# Ethernet.net
KiCad netlist of a schematic drawn in Altium Designer
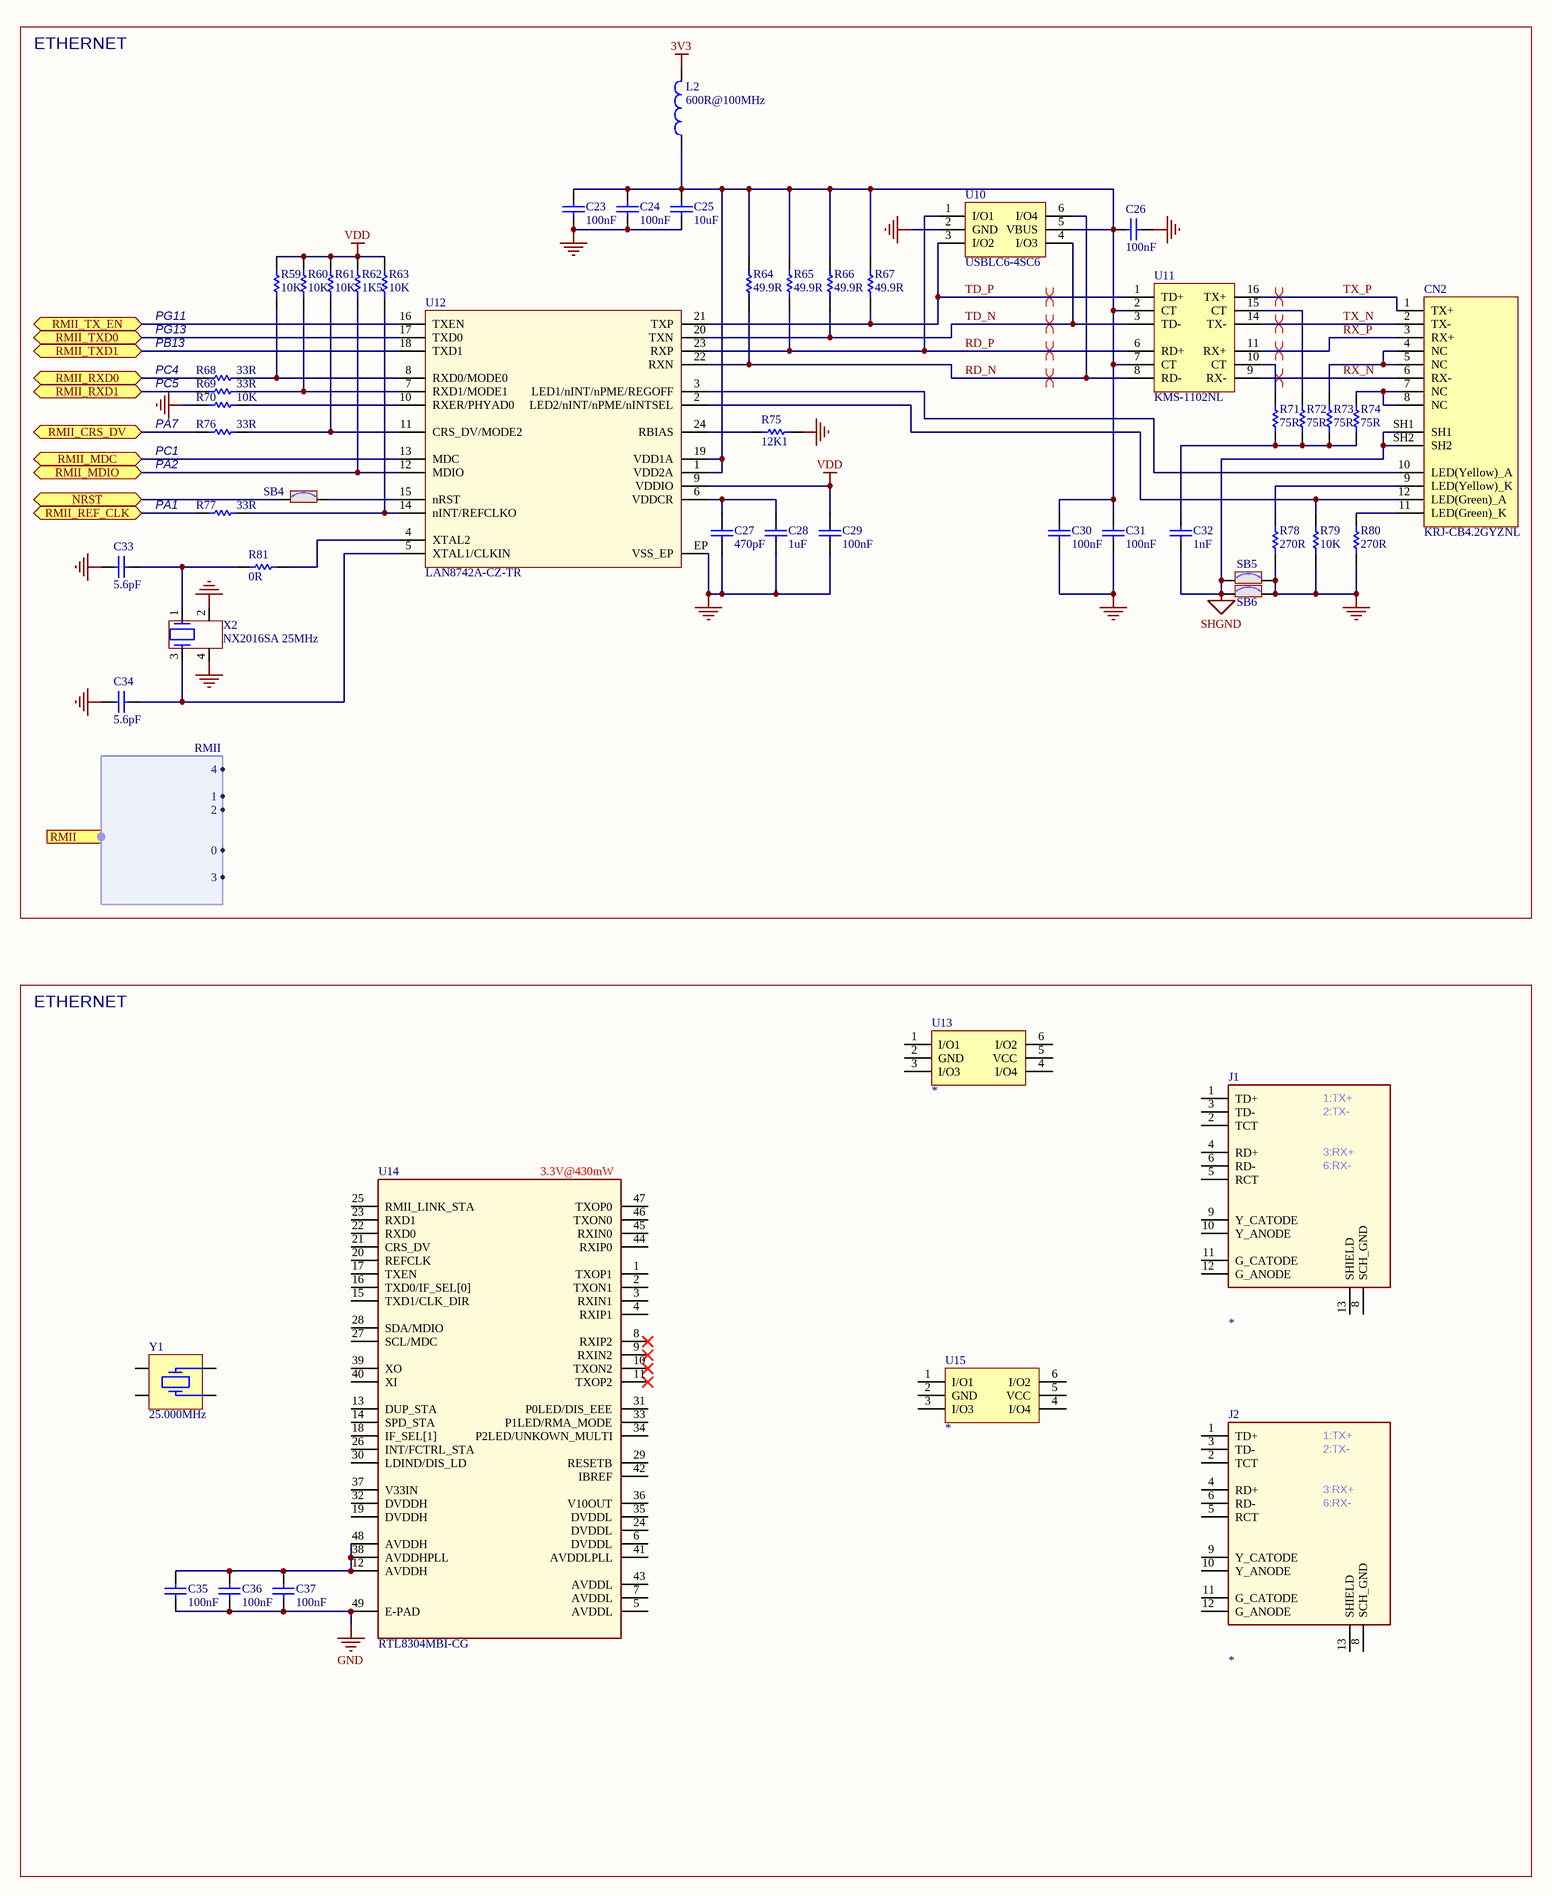
[diagram p0: Ethernet.SchDoc]

(export (version "E")
  (design (tool "Eeschema 10.0.6"))
  (components
    (comp (ref "C23")
      (value "100nF")
      (footprint "C0603")
      (description "Capacitor, MLCC, 100nF, 6V3, X5R, 10%, 0603, T=0,8mm")
      (fields
        (field (name "INTERNAL_PART_NUMBER") "MCD-00237")
        (field (name "MANUFACTURER_PART_NUMBER") "CC0603KRX5R5BB104")
        (field (name "PROVIDED_BY") "SUBCO")
      )
      (libsource (lib "MCD_PARTS_database") (part "Capacitor"))
    )
    (comp (ref "C24")
      (value "100nF")
      (footprint "C0603")
      (description "Capacitor, MLCC, 100nF, 6V3, X5R, 10%, 0603, T=0,8mm")
      (fields
        (field (name "INTERNAL_PART_NUMBER") "MCD-00237")
        (field (name "MANUFACTURER_PART_NUMBER") "CC0603KRX5R5BB104")
        (field (name "PROVIDED_BY") "SUBCO")
      )
      (libsource (lib "MCD_PARTS_database") (part "Capacitor"))
    )
    (comp (ref "C25")
      (value "10uF")
      (footprint "C0603")
      (description "Capacitor, MLCC, 10µF, 10V, X5R, 10%, 0603, T=0.8mm")
      (fields
        (field (name "INTERNAL_PART_NUMBER") "MCD-01124")
        (field (name "MANUFACTURER_PART_NUMBER") "GRM188R61A106KAAL")
        (field (name "PROVIDED_BY") "SUBCO")
      )
      (libsource (lib "MCD_PARTS_database") (part "Capacitor"))
    )
    (comp (ref "C26")
      (value "100nF")
      (footprint "C0603")
      (description "Capacitor, MLCC, 100nF, 6V3, X5R, 10%, 0603, T=0,8mm")
      (fields
        (field (name "INTERNAL_PART_NUMBER") "MCD-00237")
        (field (name "MANUFACTURER_PART_NUMBER") "CC0603KRX5R5BB104")
        (field (name "PROVIDED_BY") "SUBCO")
      )
      (libsource (lib "MCD_PARTS_database") (part "Capacitor"))
    )
    (comp (ref "C27")
      (value "470pF")
      (footprint "C0402")
      (description "Capacitor, MLCC, 470pF, 50V, NPO, 5%, 0402, T=0,5mm")
      (fields
        (field (name "INTERNAL_PART_NUMBER") "MCD-00724")
        (field (name "MANUFACTURER_PART_NUMBER") "CC0402JRNPO9BN471")
        (field (name "PROVIDED_BY") "SUBCO")
      )
      (libsource (lib "MCD_PARTS_database") (part "Capacitor"))
    )
    (comp (ref "C28")
      (value "1uF")
      (footprint "C0402")
      (description "Capacitor, MLCC, 1uF, 6V3, X5R, 10%, 0402, T=0,5mm")
      (fields
        (field (name "INTERNAL_PART_NUMBER") "MCD-00095")
        (field (name "MANUFACTURER_PART_NUMBER") "GRM155R61E105KA12")
        (field (name "PROVIDED_BY") "SUBCO")
      )
      (libsource (lib "MCD_PARTS_database") (part "Capacitor"))
    )
    (comp (ref "C29")
      (value "100nF")
      (footprint "C0603")
      (description "Capacitor, MLCC, 100nF, 6V3, X5R, 10%, 0603, T=0,8mm")
      (fields
        (field (name "INTERNAL_PART_NUMBER") "MCD-00237")
        (field (name "MANUFACTURER_PART_NUMBER") "CC0603KRX5R5BB104")
        (field (name "PROVIDED_BY") "SUBCO")
      )
      (libsource (lib "MCD_PARTS_database") (part "Capacitor"))
    )
    (comp (ref "C30")
      (value "100nF")
      (footprint "C0603")
      (description "Capacitor, MLCC, 100nF, 6V3, X5R, 10%, 0603, T=0,8mm")
      (fields
        (field (name "INTERNAL_PART_NUMBER") "MCD-00237")
        (field (name "MANUFACTURER_PART_NUMBER") "CC0603KRX5R5BB104")
        (field (name "PROVIDED_BY") "SUBCO")
      )
      (libsource (lib "MCD_PARTS_database") (part "Capacitor"))
    )
    (comp (ref "C31")
      (value "100nF")
      (footprint "C0603")
      (description "Capacitor, MLCC, 100nF, 6V3, X5R, 10%, 0603, T=0,8mm")
      (fields
        (field (name "INTERNAL_PART_NUMBER") "MCD-00237")
        (field (name "MANUFACTURER_PART_NUMBER") "CC0603KRX5R5BB104")
        (field (name "PROVIDED_BY") "SUBCO")
      )
      (libsource (lib "MCD_PARTS_database") (part "Capacitor"))
    )
    (comp (ref "C32")
      (value "1nF")
      (footprint "C1206_H1P6")
      (description "Capacitor, MLCC, 1nF, 2KV, X7R, 10%, 1206, T=1,25mm")
      (fields
        (field (name "INTERNAL_PART_NUMBER") "MCD-00722")
        (field (name "MANUFACTURER_PART_NUMBER") "CC1206KKX7RDBB102")
        (field (name "PROVIDED_BY") "SUBCO")
      )
      (libsource (lib "MCD_PARTS_database") (part "Capacitor"))
    )
    (comp (ref "C33")
      (value "5.6pF")
      (footprint "C0402")
      (description "Capacitor, MLCC, 5.6pF, 50V, NPO, 5%, 0402, T=0,5mm")
      (fields
        (field (name "INTERNAL_PART_NUMBER") "MCD-01374")
        (field (name "MANUFACTURER_PART_NUMBER") "CC0402BRNPO9BN5R6")
        (field (name "PROVIDED_BY") "SUBCO")
      )
      (libsource (lib "MCD_PARTS_database") (part "Capacitor"))
    )
    (comp (ref "C34")
      (value "5.6pF")
      (footprint "C0402")
      (description "Capacitor, MLCC, 5.6pF, 50V, NPO, 5%, 0402, T=0,5mm")
      (fields
        (field (name "INTERNAL_PART_NUMBER") "MCD-01374")
        (field (name "MANUFACTURER_PART_NUMBER") "CC0402BRNPO9BN5R6")
        (field (name "PROVIDED_BY") "SUBCO")
      )
      (libsource (lib "MCD_PARTS_database") (part "Capacitor"))
    )
    (comp (ref "C35")
      (value "100nF")
      (footprint "C0603")
      (description "Capacitor, MLCC, 100nF, 6V3, X5R, 10%, 0603, T=0,8mm")
      (fields
        (field (name "INTERNAL_PART_NUMBER") "MCD-00237")
        (field (name "MANUFACTURER_PART_NUMBER") "CC0603KRX5R5BB104")
        (field (name "PROVIDED_BY") "SUBCO")
      )
      (libsource (lib "Motherboard") (part "Capacitor_1"))
    )
    (comp (ref "C36")
      (value "100nF")
      (footprint "C0603")
      (description "Capacitor, MLCC, 100nF, 6V3, X5R, 10%, 0603, T=0,8mm")
      (fields
        (field (name "INTERNAL_PART_NUMBER") "MCD-00237")
        (field (name "MANUFACTURER_PART_NUMBER") "CC0603KRX5R5BB104")
        (field (name "PROVIDED_BY") "SUBCO")
      )
      (libsource (lib "Motherboard") (part "Capacitor_1"))
    )
    (comp (ref "C37")
      (value "100nF")
      (footprint "C0603")
      (description "Capacitor, MLCC, 100nF, 6V3, X5R, 10%, 0603, T=0,8mm")
      (fields
        (field (name "INTERNAL_PART_NUMBER") "MCD-00237")
        (field (name "MANUFACTURER_PART_NUMBER") "CC0603KRX5R5BB104")
        (field (name "PROVIDED_BY") "SUBCO")
      )
      (libsource (lib "Motherboard") (part "Capacitor_1"))
    )
    (comp (ref "CN2")
      (value "KRJ-CB4.2GYZNL")
      (footprint "CON_RJ45_DGKYD_KRJ-CB4.2GYZNL")
      (description "RJ45 jack, single port, with LEDS, Metal shielded dip low profile")
      (fields
        (field (name "INTERNAL_PART_NUMBER") "MCD-00717")
        (field (name "MANUFACTURER") "DONGGUAN KEYOUDA ELECTRONIC TECHNOLOGY")
        (field (name "PROVIDED_BY") "SUBCO")
      )
      (libsource (lib "MCD_PARTS_database") (part "RJ45_KRJ-CB4.2GYZNL"))
    )
    (comp (ref "J1")
      (value "*")
      (footprint "L829-1J1T-43")
      (description "CONN MAGJACK 1PORT SHLD 1000BT")
      (fields
        (field (name "MANUFACTURER") "Bel Fuse Inc")
        (field (name "MANUFACTURER PART NUMBER") "L829-1J1T-43")
        (field (name ".CHECKED PCB") "RF")
        (field (name ".CHECKED SCH") "RF")
      )
      (libsource (lib "Motherboard") (part "51F-1203GYDZ2NL"))
    )
    (comp (ref "J2")
      (value "*")
      (footprint "L829-1J1T-43")
      (description "CONN MAGJACK 1PORT SHLD 1000BT")
      (fields
        (field (name "MANUFACTURER") "Bel Fuse Inc")
        (field (name "MANUFACTURER PART NUMBER") "L829-1J1T-43")
        (field (name ".CHECKED PCB") "RF")
        (field (name ".CHECKED SCH") "RF")
      )
      (libsource (lib "Motherboard") (part "51F-1203GYDZ2NL"))
    )
    (comp (ref "L2")
      (value "600R@100MHz")
      (footprint "L0603")
      (description "SMD Chip ferrite bead, 600R@100MHz +/-25%, 350mA, 500mohm DC, 0603, T=0.8mm")
      (fields
        (field (name "INTERNAL_PART_NUMBER") "MCD-00047")
        (field (name "MANUFACTURER_PART_NUMBER") "FCM1608KF-601T03")
        (field (name "PROVIDED_BY") "SUBCO")
      )
      (libsource (lib "MCD_PARTS_database") (part "BEAD"))
    )
    (comp (ref "R59")
      (value "10K")
      (footprint "R0402")
      (description "Resistor,10K,0402,1%,1/16W")
      (fields
        (field (name "INTERNAL_PART_NUMBER") "MCD-00053")
        (field (name "MANUFACTURER_PART_NUMBER") "RC0402FR-0710KL")
        (field (name "PROVIDED_BY") "SUBCO")
      )
      (libsource (lib "MCD_PARTS_database") (part "Resistor"))
    )
    (comp (ref "R60")
      (value "10K")
      (footprint "R0402")
      (description "Resistor,10K,0402,1%,1/16W")
      (fields
        (field (name "INTERNAL_PART_NUMBER") "MCD-00053")
        (field (name "MANUFACTURER_PART_NUMBER") "RC0402FR-0710KL")
        (field (name "PROVIDED_BY") "SUBCO")
      )
      (libsource (lib "MCD_PARTS_database") (part "Resistor"))
    )
    (comp (ref "R61")
      (value "10K")
      (footprint "R0402")
      (description "Resistor,10K,0402,1%,1/16W")
      (fields
        (field (name "INTERNAL_PART_NUMBER") "MCD-00053")
        (field (name "MANUFACTURER_PART_NUMBER") "RC0402FR-0710KL")
        (field (name "PROVIDED_BY") "SUBCO")
      )
      (libsource (lib "MCD_PARTS_database") (part "Resistor"))
    )
    (comp (ref "R62")
      (value "1K5")
      (footprint "R0402")
      (description "Resistor,1K5,0402,1%,1/16W")
      (fields
        (field (name "INTERNAL_PART_NUMBER") "MCD-00068")
        (field (name "MANUFACTURER_PART_NUMBER") "RC0402FR-071K5L")
        (field (name "PROVIDED_BY") "SUBCO")
      )
      (libsource (lib "MCD_PARTS_database") (part "Resistor"))
    )
    (comp (ref "R63")
      (value "10K")
      (footprint "R0402")
      (description "Resistor,10K,0402,1%,1/16W")
      (fields
        (field (name "INTERNAL_PART_NUMBER") "MCD-00053")
        (field (name "MANUFACTURER_PART_NUMBER") "RC0402FR-0710KL")
        (field (name "PROVIDED_BY") "SUBCO")
      )
      (libsource (lib "MCD_PARTS_database") (part "Resistor"))
    )
    (comp (ref "R64")
      (value "49.9R")
      (footprint "R0402")
      (description "Resistor,49R9,0402,1%,1/16W")
      (fields
        (field (name "INTERNAL_PART_NUMBER") "MCD-00565")
        (field (name "MANUFACTURER_PART_NUMBER") "RC0402FR-0749R9L")
        (field (name "PROVIDED_BY") "SUBCO")
      )
      (libsource (lib "MCD_PARTS_database") (part "Resistor"))
    )
    (comp (ref "R65")
      (value "49.9R")
      (footprint "R0402")
      (description "Resistor,49R9,0402,1%,1/16W")
      (fields
        (field (name "INTERNAL_PART_NUMBER") "MCD-00565")
        (field (name "MANUFACTURER_PART_NUMBER") "RC0402FR-0749R9L")
        (field (name "PROVIDED_BY") "SUBCO")
      )
      (libsource (lib "MCD_PARTS_database") (part "Resistor"))
    )
    (comp (ref "R66")
      (value "49.9R")
      (footprint "R0402")
      (description "Resistor,49R9,0402,1%,1/16W")
      (fields
        (field (name "INTERNAL_PART_NUMBER") "MCD-00565")
        (field (name "MANUFACTURER_PART_NUMBER") "RC0402FR-0749R9L")
        (field (name "PROVIDED_BY") "SUBCO")
      )
      (libsource (lib "MCD_PARTS_database") (part "Resistor"))
    )
    (comp (ref "R67")
      (value "49.9R")
      (footprint "R0402")
      (description "Resistor,49R9,0402,1%,1/16W")
      (fields
        (field (name "INTERNAL_PART_NUMBER") "MCD-00565")
        (field (name "MANUFACTURER_PART_NUMBER") "RC0402FR-0749R9L")
        (field (name "PROVIDED_BY") "SUBCO")
      )
      (libsource (lib "MCD_PARTS_database") (part "Resistor"))
    )
    (comp (ref "R68")
      (value "33R")
      (footprint "R0402")
      (description "Resistor,33R,0402,1%,1/16W")
      (fields
        (field (name "INTERNAL_PART_NUMBER") "MCD-00455")
        (field (name "MANUFACTURER_PART_NUMBER") "RC0402FR-0733RL")
        (field (name "PROVIDED_BY") "SUBCO")
      )
      (libsource (lib "MCD_PARTS_database") (part "Resistor"))
    )
    (comp (ref "R69")
      (value "33R")
      (footprint "R0402")
      (description "Resistor,33R,0402,1%,1/16W")
      (fields
        (field (name "INTERNAL_PART_NUMBER") "MCD-00455")
        (field (name "MANUFACTURER_PART_NUMBER") "RC0402FR-0733RL")
        (field (name "PROVIDED_BY") "SUBCO")
      )
      (libsource (lib "MCD_PARTS_database") (part "Resistor"))
    )
    (comp (ref "R70")
      (value "10K")
      (footprint "R0402")
      (description "Resistor,10K,0402,1%,1/16W")
      (fields
        (field (name "INTERNAL_PART_NUMBER") "MCD-00053")
        (field (name "MANUFACTURER_PART_NUMBER") "RC0402FR-0710KL")
        (field (name "PROVIDED_BY") "SUBCO")
      )
      (libsource (lib "MCD_PARTS_database") (part "Resistor"))
    )
    (comp (ref "R71")
      (value "75R")
      (footprint "R0402")
      (description "Resistor,75R,0402,1%,1/16W")
      (fields
        (field (name "INTERNAL_PART_NUMBER") "MCD-00515")
        (field (name "MANUFACTURER_PART_NUMBER") "RC0402FR-0775RL")
        (field (name "PROVIDED_BY") "SUBCO")
      )
      (libsource (lib "MCD_PARTS_database") (part "Resistor"))
    )
    (comp (ref "R72")
      (value "75R")
      (footprint "R0402")
      (description "Resistor,75R,0402,1%,1/16W")
      (fields
        (field (name "INTERNAL_PART_NUMBER") "MCD-00515")
        (field (name "MANUFACTURER_PART_NUMBER") "RC0402FR-0775RL")
        (field (name "PROVIDED_BY") "SUBCO")
      )
      (libsource (lib "MCD_PARTS_database") (part "Resistor"))
    )
    (comp (ref "R73")
      (value "75R")
      (footprint "R0402")
      (description "Resistor,75R,0402,1%,1/16W")
      (fields
        (field (name "INTERNAL_PART_NUMBER") "MCD-00515")
        (field (name "MANUFACTURER_PART_NUMBER") "RC0402FR-0775RL")
        (field (name "PROVIDED_BY") "SUBCO")
      )
      (libsource (lib "MCD_PARTS_database") (part "Resistor"))
    )
    (comp (ref "R74")
      (value "75R")
      (footprint "R0402")
      (description "Resistor,75R,0402,1%,1/16W")
      (fields
        (field (name "INTERNAL_PART_NUMBER") "MCD-00515")
        (field (name "MANUFACTURER_PART_NUMBER") "RC0402FR-0775RL")
        (field (name "PROVIDED_BY") "SUBCO")
      )
      (libsource (lib "MCD_PARTS_database") (part "Resistor"))
    )
    (comp (ref "R75")
      (value "12K1")
      (footprint "R0402")
      (description "Resistor,12K1,0402,1%,1/16W")
      (fields
        (field (name "INTERNAL_PART_NUMBER") "MCD-00723")
        (field (name "MANUFACTURER_PART_NUMBER") "RC0402FR-0712K1L")
        (field (name "PROVIDED_BY") "SUBCO")
      )
      (libsource (lib "MCD_PARTS_database") (part "Resistor"))
    )
    (comp (ref "R76")
      (value "33R")
      (footprint "R0402")
      (description "Resistor,33R,0402,1%,1/16W")
      (fields
        (field (name "INTERNAL_PART_NUMBER") "MCD-00455")
        (field (name "MANUFACTURER_PART_NUMBER") "RC0402FR-0733RL")
        (field (name "PROVIDED_BY") "SUBCO")
      )
      (libsource (lib "MCD_PARTS_database") (part "Resistor"))
    )
    (comp (ref "R77")
      (value "33R")
      (footprint "R0402")
      (description "Resistor,33R,0402,1%,1/16W")
      (fields
        (field (name "INTERNAL_PART_NUMBER") "MCD-00455")
        (field (name "MANUFACTURER_PART_NUMBER") "RC0402FR-0733RL")
        (field (name "PROVIDED_BY") "SUBCO")
      )
      (libsource (lib "MCD_PARTS_database") (part "Resistor"))
    )
    (comp (ref "R78")
      (value "270R")
      (footprint "R0402")
      (description "Resistor,270R,0402,1%,1/16W")
      (fields
        (field (name "INTERNAL_PART_NUMBER") "MCD-00441")
        (field (name "MANUFACTURER_PART_NUMBER") "RC0402FR-07270RL")
        (field (name "PROVIDED_BY") "SUBCO")
      )
      (libsource (lib "MCD_PARTS_database") (part "Resistor"))
    )
    (comp (ref "R79")
      (value "10K")
      (footprint "R0402")
      (description "Resistor,10K,0402,1%,1/16W")
      (fields
        (field (name "INTERNAL_PART_NUMBER") "MCD-00053")
        (field (name "MANUFACTURER_PART_NUMBER") "RC0402FR-0710KL")
        (field (name "PROVIDED_BY") "SUBCO")
      )
      (libsource (lib "MCD_PARTS_database") (part "Resistor"))
    )
    (comp (ref "R80")
      (value "270R")
      (footprint "R0402")
      (description "Resistor,270R,0402,1%,1/16W")
      (fields
        (field (name "INTERNAL_PART_NUMBER") "MCD-00441")
        (field (name "MANUFACTURER_PART_NUMBER") "RC0402FR-07270RL")
        (field (name "PROVIDED_BY") "SUBCO")
      )
      (libsource (lib "MCD_PARTS_database") (part "Resistor"))
    )
    (comp (ref "R81")
      (value "0R")
      (footprint "R0402")
      (description "Resistor,0R,0402,5%,1/16W")
      (fields
        (field (name "INTERNAL_PART_NUMBER") "MCD-00052")
        (field (name "MANUFACTURER_PART_NUMBER") "RC0402JR-070RL")
        (field (name "PROVIDED_BY") "SUBCO")
      )
      (libsource (lib "MCD_PARTS_database") (part "Resistor"))
    )
    (comp (ref "SB4")
      (value "SB_ON")
      (footprint "SOLDER-BRIDGE_R0603-0R")
      (description "Solder Bridge ON")
      (fields
        (field (name "INTERNAL_PART_NUMBER") "MCD-00071")
        (field (name "MANUFACTURER_PART_NUMBER") "RC0603JR-070RL")
        (field (name "PROVIDED_BY") "SUBCO")
      )
      (libsource (lib "MCD_PARTS_database") (part "SB_ON"))
    )
    (comp (ref "SB5")
      (value "SB_ON")
      (footprint "SOLDER-BRIDGE_R0603-0R")
      (description "Solder Bridge ON")
      (fields
        (field (name "INTERNAL_PART_NUMBER") "MCD-00071")
        (field (name "MANUFACTURER_PART_NUMBER") "RC0603JR-070RL")
        (field (name "PROVIDED_BY") "SUBCO")
      )
      (libsource (lib "MCD_PARTS_database") (part "SB_ON"))
    )
    (comp (ref "SB6")
      (value "SB_ON")
      (footprint "SOLDER-BRIDGE_R0603-0R")
      (description "Solder Bridge ON")
      (fields
        (field (name "INTERNAL_PART_NUMBER") "MCD-00071")
        (field (name "MANUFACTURER_PART_NUMBER") "RC0603JR-070RL")
        (field (name "PROVIDED_BY") "SUBCO")
      )
      (libsource (lib "MCD_PARTS_database") (part "SB_ON"))
    )
    (comp (ref "U10")
      (value "USBLC6-4SC6")
      (footprint "ESD_SOT23-6L")
      (description "Very low capacitance ESD protection , 4 lines")
      (fields
        (field (name "INTERNAL_PART_NUMBER") "MCD-00250")
        (field (name "MANUFACTURER") "STMICROELECTRONICS")
        (field (name "PROVIDED_BY") "SUBCO with ST control")
      )
      (libsource (lib "MCD_PARTS_database") (part "USBLC6-4SC6"))
    )
    (comp (ref "U11")
      (value "KMS-1102NL")
      (footprint "TRS_DGKYD_KMS-1102NL")
      (description "Discrete Magnetic Transformer Module, 16 pins, SMT, 100 Base-TX")
      (fields
        (field (name "INTERNAL_PART_NUMBER") "MCD-00718")
        (field (name "MANUFACTURER") "DONGGUAN KEYOUDA ELECTRONIC TECHNOLOGY")
        (field (name "PROVIDED_BY") "SUBCO")
      )
      (libsource (lib "MCD_PARTS_database") (part "KMS-1102NL"))
    )
    (comp (ref "U12")
      (value "LAN8742A-CZ-TR")
      (footprint "ICC_VQFN24-EPAD_4X4_P050")
      (description "10/100M RMII Ethernet transceiver")
      (fields
        (field (name "INTERNAL_PART_NUMBER") "MCD-00719")
        (field (name "MANUFACTURER") "MICROCHIP")
        (field (name "PROVIDED_BY") "SUBCO")
      )
      (libsource (lib "MCD_PARTS_database") (part "LAN8742A-CZ-TR"))
    )
    (comp (ref "U13")
      (value "*")
      (footprint "ESD_SOT23-6L")
      (description "Very low capacitance ESD protection , 4 lines")
      (fields
        (field (name "INTERNAL_PART_NUMBER") "MCD-00250")
        (field (name "MANUFACTURER_PART_NUMBER") "USBLC6-4SC6")
        (field (name "ALTIUM_VALUE") "*")
        (field (name "PROVIDED_BY") "SUBCO with ST control")
      )
      (libsource (lib "Motherboard") (part "ESDU5V0K4"))
    )
    (comp (ref "U14")
      (value "RTL8304MBI-CG")
      (footprint "QFN48_SMALL_EP_7MMX7MM")
      (description "SINGLE-CHIP 4-PORT 10/100M ETHERNET SWITCH CONTROLLER")
      (fields
        (field (name "MANUFACTURER") "REALTEK")
        (field (name ".CREATOR") "MM")
        (field (name ".CHECKED PCB") "MM")
        (field (name ".CHECKED SCH") "MM")
      )
      (libsource (lib "Motherboard") (part "RTL8304MBI-CG"))
    )
    (comp (ref "U15")
      (value "*")
      (footprint "ESD_SOT23-6L")
      (description "Very low capacitance ESD protection , 4 lines")
      (fields
        (field (name "INTERNAL_PART_NUMBER") "MCD-00250")
        (field (name "MANUFACTURER_PART_NUMBER") "USBLC6-4SC6")
        (field (name "ALTIUM_VALUE") "*")
        (field (name "PROVIDED_BY") "SUBCO with ST control")
      )
      (libsource (lib "Motherboard") (part "ESDU5V0K4"))
    )
    (comp (ref "X2")
      (value "NX2016SA 25MHz")
      (footprint "CRY_NX2016SA_4P")
      (description "Crystal 25MHz, 6pF, +-20ppm, 80ohms max, SMD")
      (fields
        (field (name "INTERNAL_PART_NUMBER") "MCD-01364")
        (field (name "MANUFACTURER_PART_NUMBER") "NX2016SA 25MHz EXS00A-CS11321")
        (field (name "PROVIDED_BY") "SUBCO")
      )
      (libsource (lib "MCD_PARTS_database") (part "XTAL_4_PINS"))
    )
    (comp (ref "Y1")
      (value "25.000MHz")
      (footprint "ABM8G")
      (description "CRYSTAL 25MHZ 18PF SMD")
      (fields
        (field (name "MANUFACTURER") "Abracon Corporation")
        (field (name "MANUFACTURER PART NUMBER") "ABM8G-25.000MHZ-18-D2Y-T")
        (field (name ".CHECKED PCB") "MM")
        (field (name ".CHECKED SCH") "MM")
        (field (name ".CREATOR") "MM")
      )
      (libsource (lib "Motherboard") (part "ABM8G-25.000MHZ-18-D2Y-T"))
    )
  )
  (nets
    (net (code "2") (name "/NRST") (class "Default")
      (node (ref "SB4") (pin "1") (pinfunction "1_1") (pintype "passive"))
    )
    (net (code "3") (name "/RD_N") (class "Default")
      (node (ref "R64") (pin "1") (pinfunction "1_1") (pintype "passive"))
      (node (ref "U10") (pin "6") (pinfunction "I/O4_6") (pintype "passive"))
      (node (ref "U11") (pin "8") (pinfunction "RD-_8") (pintype "passive"))
      (node (ref "U12") (pin "22") (pinfunction "RXN_22") (pintype "passive"))
    )
    (net (code "4") (name "/RD_P") (class "Default")
      (node (ref "R65") (pin "1") (pinfunction "1_1") (pintype "passive"))
      (node (ref "U10") (pin "1") (pinfunction "I/O1_1") (pintype "passive"))
      (node (ref "U11") (pin "6") (pinfunction "RD+_6") (pintype "passive"))
      (node (ref "U12") (pin "23") (pinfunction "RXP_23") (pintype "passive"))
    )
    (net (code "5") (name "/RMII_CRS_DV") (class "Default")
      (node (ref "R76") (pin "1") (pinfunction "1_1") (pintype "passive"))
    )
    (net (code "6") (name "/RMII_MDC") (class "Default")
      (node (ref "U12") (pin "13") (pinfunction "MDC_13") (pintype "passive"))
    )
    (net (code "7") (name "/RMII_MDIO") (class "Default")
      (node (ref "R62") (pin "1") (pinfunction "1_1") (pintype "passive"))
      (node (ref "U12") (pin "12") (pinfunction "MDIO_12") (pintype "passive"))
    )
    (net (code "8") (name "/RMII_REF_CLK") (class "Default")
      (node (ref "R77") (pin "1") (pinfunction "1_1") (pintype "passive"))
    )
    (net (code "9") (name "/RMII_RXD0") (class "Default")
      (node (ref "R68") (pin "1") (pinfunction "1_1") (pintype "passive"))
    )
    (net (code "10") (name "/RMII_RXD1") (class "Default")
      (node (ref "R69") (pin "1") (pinfunction "1_1") (pintype "passive"))
    )
    (net (code "11") (name "/RMII_TXD0") (class "Default")
      (node (ref "U12") (pin "17") (pinfunction "TXD0_17") (pintype "passive"))
    )
    (net (code "12") (name "/RMII_TXD1") (class "Default")
      (node (ref "U12") (pin "18") (pinfunction "TXD1_18") (pintype "passive"))
    )
    (net (code "13") (name "/RMII_TX_EN") (class "Default")
      (node (ref "U12") (pin "16") (pinfunction "TXEN_16") (pintype "passive"))
    )
    (net (code "14") (name "/RX_N") (class "Default")
      (node (ref "CN2") (pin "6") (pinfunction "RX-_6") (pintype "passive"))
      (node (ref "U11") (pin "9") (pinfunction "RX-_9") (pintype "passive"))
    )
    (net (code "15") (name "/RX_P") (class "Default")
      (node (ref "CN2") (pin "3") (pinfunction "RX+_3") (pintype "passive"))
      (node (ref "U11") (pin "11") (pinfunction "RX+_11") (pintype "passive"))
    )
    (net (code "16") (name "/TD_N") (class "Default")
      (node (ref "R66") (pin "1") (pinfunction "1_1") (pintype "passive"))
      (node (ref "U10") (pin "4") (pinfunction "I/O3_4") (pintype "passive"))
      (node (ref "U11") (pin "3") (pinfunction "TD-_3") (pintype "passive"))
      (node (ref "U12") (pin "20") (pinfunction "TXN_20") (pintype "passive"))
    )
    (net (code "17") (name "/TD_P") (class "Default")
      (node (ref "R67") (pin "1") (pinfunction "1_1") (pintype "passive"))
      (node (ref "U10") (pin "3") (pinfunction "I/O2_3") (pintype "passive"))
      (node (ref "U11") (pin "1") (pinfunction "TD+_1") (pintype "passive"))
      (node (ref "U12") (pin "21") (pinfunction "TXP_21") (pintype "passive"))
    )
    (net (code "18") (name "/TX_N") (class "Default")
      (node (ref "CN2") (pin "2") (pinfunction "TX-_2") (pintype "passive"))
      (node (ref "U11") (pin "14") (pinfunction "TX-_14") (pintype "passive"))
    )
    (net (code "19") (name "/TX_P") (class "Default")
      (node (ref "CN2") (pin "1") (pinfunction "TX+_1") (pintype "passive"))
      (node (ref "U11") (pin "16") (pinfunction "TX+_16") (pintype "passive"))
    )
    (net (code "21") (name "3V3") (class "Default")
      (node (ref "L2") (pin "2") (pinfunction "2_2") (pintype "passive"))
    )
    (net (code "22") (name "GND") (class "Default")
      (node (ref "C23") (pin "1") (pinfunction "1_1") (pintype "passive"))
      (node (ref "C24") (pin "1") (pinfunction "1_1") (pintype "passive"))
      (node (ref "C25") (pin "1") (pinfunction "1_1") (pintype "passive"))
      (node (ref "C26") (pin "2") (pinfunction "2_2") (pintype "passive"))
      (node (ref "C27") (pin "1") (pinfunction "1_1") (pintype "passive"))
      (node (ref "C28") (pin "1") (pinfunction "1_1") (pintype "passive"))
      (node (ref "C29") (pin "1") (pinfunction "1_1") (pintype "passive"))
      (node (ref "C30") (pin "1") (pinfunction "1_1") (pintype "passive"))
      (node (ref "C31") (pin "1") (pinfunction "1_1") (pintype "passive"))
      (node (ref "C33") (pin "1") (pinfunction "1_1") (pintype "passive"))
      (node (ref "C34") (pin "1") (pinfunction "1_1") (pintype "passive"))
      (node (ref "C35") (pin "1") (pinfunction "1_1") (pintype "passive"))
      (node (ref "C36") (pin "1") (pinfunction "1_1") (pintype "passive"))
      (node (ref "C37") (pin "1") (pinfunction "1_1") (pintype "passive"))
      (node (ref "R70") (pin "2") (pinfunction "2_2") (pintype "passive"))
      (node (ref "R75") (pin "2") (pinfunction "2_2") (pintype "passive"))
      (node (ref "R78") (pin "1") (pinfunction "1_1") (pintype "passive"))
      (node (ref "R79") (pin "1") (pinfunction "1_1") (pintype "passive"))
      (node (ref "R80") (pin "1") (pinfunction "1_1") (pintype "passive"))
      (node (ref "SB5") (pin "2") (pinfunction "2_2") (pintype "passive"))
      (node (ref "SB6") (pin "2") (pinfunction "2_2") (pintype "passive"))
      (node (ref "U10") (pin "2") (pinfunction "GND_2") (pintype "passive"))
      (node (ref "U12") (pin "EP") (pinfunction "VSS_EP_EP") (pintype "passive"))
      (node (ref "U14") (pin "49") (pinfunction "E-PAD_49") (pintype "passive"))
      (node (ref "X2") (pin "2") (pinfunction "2_2") (pintype "passive"))
      (node (ref "X2") (pin "4") (pinfunction "4_4") (pintype "passive"))
    )
    (net (code "23") (name "Net-(C32-Pad2)") (class "Default")
      (node (ref "C32") (pin "2") (pinfunction "2_2") (pintype "passive"))
      (node (ref "R71") (pin "1") (pinfunction "1_1") (pintype "passive"))
      (node (ref "R72") (pin "1") (pinfunction "1_1") (pintype "passive"))
      (node (ref "R73") (pin "1") (pinfunction "1_1") (pintype "passive"))
      (node (ref "R74") (pin "1") (pinfunction "1_1") (pintype "passive"))
    )
    (net (code "24") (name "Net-(C33-Pad2)") (class "Default")
      (node (ref "C33") (pin "2") (pinfunction "2_2") (pintype "passive"))
      (node (ref "R81") (pin "1") (pinfunction "1_1") (pintype "passive"))
      (node (ref "X2") (pin "1") (pinfunction "1_1") (pintype "passive"))
    )
    (net (code "25") (name "Net-(CN2-LED(Green)_A)") (class "Default")
      (node (ref "CN2") (pin "12") (pinfunction "LED(Green)_A_12") (pintype "passive"))
      (node (ref "R79") (pin "2") (pinfunction "2_2") (pintype "passive"))
      (node (ref "U12") (pin "2") (pinfunction "LED2/nINT/nPME/nINTSEL_2") (pintype "passive"))
    )
    (net (code "26") (name "Net-(CN2-LED(Green)_K)") (class "Default")
      (node (ref "CN2") (pin "11") (pinfunction "LED(Green)_K_11") (pintype "passive"))
      (node (ref "R80") (pin "2") (pinfunction "2_2") (pintype "passive"))
    )
    (net (code "27") (name "Net-(CN2-LED(Yellow)_A)") (class "Default")
      (node (ref "CN2") (pin "10") (pinfunction "LED(Yellow)_A_10") (pintype "passive"))
      (node (ref "U12") (pin "3") (pinfunction "LED1/nINT/nPME/REGOFF_3") (pintype "passive"))
    )
    (net (code "28") (name "Net-(CN2-LED(Yellow)_K)") (class "Default")
      (node (ref "CN2") (pin "9") (pinfunction "LED(Yellow)_K_9") (pintype "passive"))
      (node (ref "R78") (pin "2") (pinfunction "2_2") (pintype "passive"))
    )
    (net (code "29") (name "Net-(CN2-NC-Pad4)") (class "Default")
      (node (ref "CN2") (pin "4") (pinfunction "NC_4") (pintype "passive"))
      (node (ref "CN2") (pin "5") (pinfunction "NC_5") (pintype "passive"))
      (node (ref "R73") (pin "2") (pinfunction "2_2") (pintype "passive"))
    )
    (net (code "30") (name "Net-(CN2-NC-Pad7)") (class "Default")
      (node (ref "CN2") (pin "7") (pinfunction "NC_7") (pintype "passive"))
      (node (ref "CN2") (pin "8") (pinfunction "NC_8") (pintype "passive"))
      (node (ref "R74") (pin "2") (pinfunction "2_2") (pintype "passive"))
    )
    (net (code "31") (name "Net-(R71-Pad2)") (class "Default")
      (node (ref "R71") (pin "2") (pinfunction "2_2") (pintype "passive"))
      (node (ref "U11") (pin "10") (pinfunction "CT_10") (pintype "passive"))
    )
    (net (code "32") (name "Net-(R72-Pad2)") (class "Default")
      (node (ref "R72") (pin "2") (pinfunction "2_2") (pintype "passive"))
      (node (ref "U11") (pin "15") (pinfunction "CT_15") (pintype "passive"))
    )
    (net (code "33") (name "Net-(U10-VBUS)") (class "Default")
      (node (ref "C23") (pin "2") (pinfunction "2_2") (pintype "passive"))
      (node (ref "C24") (pin "2") (pinfunction "2_2") (pintype "passive"))
      (node (ref "C25") (pin "2") (pinfunction "2_2") (pintype "passive"))
      (node (ref "C26") (pin "1") (pinfunction "1_1") (pintype "passive"))
      (node (ref "C30") (pin "2") (pinfunction "2_2") (pintype "passive"))
      (node (ref "C31") (pin "2") (pinfunction "2_2") (pintype "passive"))
      (node (ref "L2") (pin "1") (pinfunction "1_1") (pintype "passive"))
      (node (ref "R64") (pin "2") (pinfunction "2_2") (pintype "passive"))
      (node (ref "R65") (pin "2") (pinfunction "2_2") (pintype "passive"))
      (node (ref "R66") (pin "2") (pinfunction "2_2") (pintype "passive"))
      (node (ref "R67") (pin "2") (pinfunction "2_2") (pintype "passive"))
      (node (ref "U10") (pin "5") (pinfunction "VBUS_5") (pintype "passive"))
      (node (ref "U11") (pin "2") (pinfunction "CT_2") (pintype "passive"))
      (node (ref "U11") (pin "7") (pinfunction "CT_7") (pintype "passive"))
      (node (ref "U12") (pin "1") (pinfunction "VDD2A_1") (pintype "passive"))
      (node (ref "U12") (pin "19") (pinfunction "VDD1A_19") (pintype "passive"))
    )
    (net (code "34") (name "Net-(U12-CRS_DV{slash}MODE2)") (class "Default")
      (node (ref "R61") (pin "1") (pinfunction "1_1") (pintype "passive"))
      (node (ref "R76") (pin "2") (pinfunction "2_2") (pintype "passive"))
      (node (ref "U12") (pin "11") (pinfunction "CRS_DV/MODE2_11") (pintype "passive"))
    )
    (net (code "35") (name "Net-(U12-RBIAS)") (class "Default")
      (node (ref "R75") (pin "1") (pinfunction "1_1") (pintype "passive"))
      (node (ref "U12") (pin "24") (pinfunction "RBIAS_24") (pintype "passive"))
    )
    (net (code "36") (name "Net-(U12-RXD0{slash}MODE0)") (class "Default")
      (node (ref "R59") (pin "1") (pinfunction "1_1") (pintype "passive"))
      (node (ref "R68") (pin "2") (pinfunction "2_2") (pintype "passive"))
      (node (ref "U12") (pin "8") (pinfunction "RXD0/MODE0_8") (pintype "passive"))
    )
    (net (code "37") (name "Net-(U12-RXD1{slash}MODE1)") (class "Default")
      (node (ref "R60") (pin "1") (pinfunction "1_1") (pintype "passive"))
      (node (ref "R69") (pin "2") (pinfunction "2_2") (pintype "passive"))
      (node (ref "U12") (pin "7") (pinfunction "RXD1/MODE1_7") (pintype "passive"))
    )
    (net (code "38") (name "Net-(U12-RXER{slash}PHYAD0)") (class "Default")
      (node (ref "R70") (pin "1") (pinfunction "1_1") (pintype "passive"))
      (node (ref "U12") (pin "10") (pinfunction "RXER/PHYAD0_10") (pintype "passive"))
    )
    (net (code "39") (name "Net-(U12-VDDCR)") (class "Default")
      (node (ref "C27") (pin "2") (pinfunction "2_2") (pintype "passive"))
      (node (ref "C28") (pin "2") (pinfunction "2_2") (pintype "passive"))
      (node (ref "U12") (pin "6") (pinfunction "VDDCR_6") (pintype "passive"))
    )
    (net (code "40") (name "Net-(U12-XTAL1{slash}CLKIN)") (class "Default")
      (node (ref "C34") (pin "2") (pinfunction "2_2") (pintype "passive"))
      (node (ref "U12") (pin "5") (pinfunction "XTAL1/CLKIN_5") (pintype "passive"))
      (node (ref "X2") (pin "3") (pinfunction "3_3") (pintype "passive"))
    )
    (net (code "41") (name "Net-(U12-XTAL2)") (class "Default")
      (node (ref "R81") (pin "2") (pinfunction "2_2") (pintype "passive"))
      (node (ref "U12") (pin "4") (pinfunction "XTAL2_4") (pintype "passive"))
    )
    (net (code "42") (name "Net-(U12-nINT{slash}REFCLKO)") (class "Default")
      (node (ref "R63") (pin "1") (pinfunction "1_1") (pintype "passive"))
      (node (ref "R77") (pin "2") (pinfunction "2_2") (pintype "passive"))
      (node (ref "U12") (pin "14") (pinfunction "nINT/REFCLKO_14") (pintype "passive"))
    )
    (net (code "43") (name "Net-(U12-nRST)") (class "Default")
      (node (ref "SB4") (pin "2") (pinfunction "2_2") (pintype "passive"))
      (node (ref "U12") (pin "15") (pinfunction "nRST_15") (pintype "passive"))
    )
    (net (code "44") (name "Net-(U14-AVDDHPLL)") (class "Default")
      (node (ref "C35") (pin "2") (pinfunction "2_2") (pintype "passive"))
      (node (ref "C36") (pin "2") (pinfunction "2_2") (pintype "passive"))
      (node (ref "C37") (pin "2") (pinfunction "2_2") (pintype "passive"))
      (node (ref "U14") (pin "12") (pinfunction "AVDDH_12") (pintype "passive"))
      (node (ref "U14") (pin "38") (pinfunction "AVDDHPLL_38") (pintype "passive"))
      (node (ref "U14") (pin "48") (pinfunction "AVDDH_48") (pintype "passive"))
    )
    (net (code "45") (name "SHGND") (class "Default")
      (node (ref "C32") (pin "1") (pinfunction "1_1") (pintype "passive"))
      (node (ref "CN2") (pin "SH1") (pinfunction "SH1_SH1") (pintype "passive"))
      (node (ref "CN2") (pin "SH2") (pinfunction "SH2_SH2") (pintype "passive"))
      (node (ref "SB5") (pin "1") (pinfunction "1_1") (pintype "passive"))
      (node (ref "SB6") (pin "1") (pinfunction "1_1") (pintype "passive"))
    )
    (net (code "46") (name "VDD") (class "Default")
      (node (ref "C29") (pin "2") (pinfunction "2_2") (pintype "passive"))
      (node (ref "R59") (pin "2") (pinfunction "2_2") (pintype "passive"))
      (node (ref "R60") (pin "2") (pinfunction "2_2") (pintype "passive"))
      (node (ref "R61") (pin "2") (pinfunction "2_2") (pintype "passive"))
      (node (ref "R62") (pin "2") (pinfunction "2_2") (pintype "passive"))
      (node (ref "R63") (pin "2") (pinfunction "2_2") (pintype "passive"))
      (node (ref "U12") (pin "9") (pinfunction "VDDIO_9") (pintype "passive"))
    )
    (net (code "47") (name "unconnected-(J1-G_ANODE-Pad12)") (class "Default")
      (node (ref "J1") (pin "12") (pinfunction "G_ANODE_12") (pintype "passive"))
    )
    (net (code "48") (name "unconnected-(J1-G_CATODE-Pad11)") (class "Default")
      (node (ref "J1") (pin "11") (pinfunction "G_CATODE_11") (pintype "passive"))
    )
    (net (code "49") (name "unconnected-(J1-RCT-Pad5)") (class "Default")
      (node (ref "J1") (pin "5") (pinfunction "RCT_5") (pintype "passive"))
    )
    (net (code "50") (name "unconnected-(J1-RD+-Pad4)") (class "Default")
      (node (ref "J1") (pin "4") (pinfunction "RD+_4") (pintype "passive"))
    )
    (net (code "51") (name "unconnected-(J1-RD--Pad6)") (class "Default")
      (node (ref "J1") (pin "6") (pinfunction "RD-_6") (pintype "passive"))
    )
    (net (code "52") (name "unconnected-(J1-SCH_GND-Pad8)") (class "Default")
      (node (ref "J1") (pin "8") (pinfunction "SCH_GND_8") (pintype "passive"))
    )
    (net (code "53") (name "unconnected-(J1-SHIELD-Pad13)") (class "Default")
      (node (ref "J1") (pin "13") (pinfunction "SHIELD_13") (pintype "passive"))
    )
    (net (code "54") (name "unconnected-(J1-TCT-Pad2)") (class "Default")
      (node (ref "J1") (pin "2") (pinfunction "TCT_2") (pintype "passive"))
    )
    (net (code "55") (name "unconnected-(J1-TD+-Pad1)") (class "Default")
      (node (ref "J1") (pin "1") (pinfunction "TD+_1") (pintype "passive"))
    )
    (net (code "56") (name "unconnected-(J1-TD--Pad3)") (class "Default")
      (node (ref "J1") (pin "3") (pinfunction "TD-_3") (pintype "passive"))
    )
    (net (code "57") (name "unconnected-(J1-Y_ANODE-Pad10)") (class "Default")
      (node (ref "J1") (pin "10") (pinfunction "Y_ANODE_10") (pintype "passive"))
    )
    (net (code "58") (name "unconnected-(J1-Y_CATODE-Pad9)") (class "Default")
      (node (ref "J1") (pin "9") (pinfunction "Y_CATODE_9") (pintype "passive"))
    )
    (net (code "59") (name "unconnected-(J2-G_ANODE-Pad12)") (class "Default")
      (node (ref "J2") (pin "12") (pinfunction "G_ANODE_12") (pintype "passive"))
    )
    (net (code "60") (name "unconnected-(J2-G_CATODE-Pad11)") (class "Default")
      (node (ref "J2") (pin "11") (pinfunction "G_CATODE_11") (pintype "passive"))
    )
    (net (code "61") (name "unconnected-(J2-RCT-Pad5)") (class "Default")
      (node (ref "J2") (pin "5") (pinfunction "RCT_5") (pintype "passive"))
    )
    (net (code "62") (name "unconnected-(J2-RD+-Pad4)") (class "Default")
      (node (ref "J2") (pin "4") (pinfunction "RD+_4") (pintype "passive"))
    )
    (net (code "63") (name "unconnected-(J2-RD--Pad6)") (class "Default")
      (node (ref "J2") (pin "6") (pinfunction "RD-_6") (pintype "passive"))
    )
    (net (code "64") (name "unconnected-(J2-SCH_GND-Pad8)") (class "Default")
      (node (ref "J2") (pin "8") (pinfunction "SCH_GND_8") (pintype "passive"))
    )
    (net (code "65") (name "unconnected-(J2-SHIELD-Pad13)") (class "Default")
      (node (ref "J2") (pin "13") (pinfunction "SHIELD_13") (pintype "passive"))
    )
    (net (code "66") (name "unconnected-(J2-TCT-Pad2)") (class "Default")
      (node (ref "J2") (pin "2") (pinfunction "TCT_2") (pintype "passive"))
    )
    (net (code "67") (name "unconnected-(J2-TD+-Pad1)") (class "Default")
      (node (ref "J2") (pin "1") (pinfunction "TD+_1") (pintype "passive"))
    )
    (net (code "68") (name "unconnected-(J2-TD--Pad3)") (class "Default")
      (node (ref "J2") (pin "3") (pinfunction "TD-_3") (pintype "passive"))
    )
    (net (code "69") (name "unconnected-(J2-Y_ANODE-Pad10)") (class "Default")
      (node (ref "J2") (pin "10") (pinfunction "Y_ANODE_10") (pintype "passive"))
    )
    (net (code "70") (name "unconnected-(J2-Y_CATODE-Pad9)") (class "Default")
      (node (ref "J2") (pin "9") (pinfunction "Y_CATODE_9") (pintype "passive"))
    )
    (net (code "71") (name "unconnected-(U13-GND-Pad2)") (class "Default")
      (node (ref "U13") (pin "2") (pinfunction "GND_2") (pintype "passive"))
    )
    (net (code "72") (name "unconnected-(U13-I{slash}O1-Pad1)") (class "Default")
      (node (ref "U13") (pin "1") (pinfunction "I/O1_1") (pintype "passive"))
    )
    (net (code "73") (name "unconnected-(U13-I{slash}O2-Pad6)") (class "Default")
      (node (ref "U13") (pin "6") (pinfunction "I/O2_6") (pintype "passive"))
    )
    (net (code "74") (name "unconnected-(U13-I{slash}O3-Pad3)") (class "Default")
      (node (ref "U13") (pin "3") (pinfunction "I/O3_3") (pintype "passive"))
    )
    (net (code "75") (name "unconnected-(U13-I{slash}O4-Pad4)") (class "Default")
      (node (ref "U13") (pin "4") (pinfunction "I/O4_4") (pintype "passive"))
    )
    (net (code "76") (name "unconnected-(U13-VCC-Pad5)") (class "Default")
      (node (ref "U13") (pin "5") (pinfunction "VCC_5") (pintype "passive"))
    )
    (net (code "77") (name "unconnected-(U14-AVDDL-Pad5)") (class "Default")
      (node (ref "U14") (pin "5") (pinfunction "AVDDL_5") (pintype "passive"))
    )
    (net (code "78") (name "unconnected-(U14-AVDDL-Pad7)") (class "Default")
      (node (ref "U14") (pin "7") (pinfunction "AVDDL_7") (pintype "passive"))
    )
    (net (code "79") (name "unconnected-(U14-AVDDL-Pad43)") (class "Default")
      (node (ref "U14") (pin "43") (pinfunction "AVDDL_43") (pintype "passive"))
    )
    (net (code "80") (name "unconnected-(U14-AVDDLPLL-Pad41)") (class "Default")
      (node (ref "U14") (pin "41") (pinfunction "AVDDLPLL_41") (pintype "passive"))
    )
    (net (code "81") (name "unconnected-(U14-CRS_DV-Pad21)") (class "Default")
      (node (ref "U14") (pin "21") (pinfunction "CRS_DV_21") (pintype "passive"))
    )
    (net (code "82") (name "unconnected-(U14-DUP_STA-Pad13)") (class "Default")
      (node (ref "U14") (pin "13") (pinfunction "DUP_STA_13") (pintype "passive"))
    )
    (net (code "83") (name "unconnected-(U14-DVDDH-Pad19)") (class "Default")
      (node (ref "U14") (pin "19") (pinfunction "DVDDH_19") (pintype "passive"))
    )
    (net (code "84") (name "unconnected-(U14-DVDDH-Pad32)") (class "Default")
      (node (ref "U14") (pin "32") (pinfunction "DVDDH_32") (pintype "passive"))
    )
    (net (code "85") (name "unconnected-(U14-DVDDL-Pad6)") (class "Default")
      (node (ref "U14") (pin "6") (pinfunction "DVDDL_6") (pintype "passive"))
    )
    (net (code "86") (name "unconnected-(U14-DVDDL-Pad24)") (class "Default")
      (node (ref "U14") (pin "24") (pinfunction "DVDDL_24") (pintype "passive"))
    )
    (net (code "87") (name "unconnected-(U14-DVDDL-Pad35)") (class "Default")
      (node (ref "U14") (pin "35") (pinfunction "DVDDL_35") (pintype "passive"))
    )
    (net (code "88") (name "unconnected-(U14-IBREF-Pad42)") (class "Default")
      (node (ref "U14") (pin "42") (pinfunction "IBREF_42") (pintype "passive"))
    )
    (net (code "89") (name "unconnected-(U14-IF_SEL[1]-Pad18)") (class "Default")
      (node (ref "U14") (pin "18") (pinfunction "IF_SEL[1]_18") (pintype "passive"))
    )
    (net (code "90") (name "unconnected-(U14-INT{slash}FCTRL_STA-Pad26)") (class "Default")
      (node (ref "U14") (pin "26") (pinfunction "INT/FCTRL_STA_26") (pintype "passive"))
    )
    (net (code "91") (name "unconnected-(U14-LDIND{slash}DIS_LD-Pad30)") (class "Default")
      (node (ref "U14") (pin "30") (pinfunction "LDIND/DIS_LD_30") (pintype "passive"))
    )
    (net (code "92") (name "unconnected-(U14-P0LED{slash}DIS_EEE-Pad31)") (class "Default")
      (node (ref "U14") (pin "31") (pinfunction "P0LED/DIS_EEE_31") (pintype "passive"))
    )
    (net (code "93") (name "unconnected-(U14-P1LED{slash}RMA_MODE-Pad33)") (class "Default")
      (node (ref "U14") (pin "33") (pinfunction "P1LED/RMA_MODE_33") (pintype "passive"))
    )
    (net (code "94") (name "unconnected-(U14-P2LED{slash}UNKOWN_MULTI-Pad34)") (class "Default")
      (node (ref "U14") (pin "34") (pinfunction "P2LED/UNKOWN_MULTI_34") (pintype "passive"))
    )
    (net (code "95") (name "unconnected-(U14-REFCLK-Pad20)") (class "Default")
      (node (ref "U14") (pin "20") (pinfunction "REFCLK_20") (pintype "passive"))
    )
    (net (code "96") (name "unconnected-(U14-RESETB-Pad29)") (class "Default")
      (node (ref "U14") (pin "29") (pinfunction "RESETB_29") (pintype "passive"))
    )
    (net (code "97") (name "unconnected-(U14-RMII_LINK_STA-Pad25)") (class "Default")
      (node (ref "U14") (pin "25") (pinfunction "RMII_LINK_STA_25") (pintype "passive"))
    )
    (net (code "98") (name "unconnected-(U14-RXD0-Pad22)") (class "Default")
      (node (ref "U14") (pin "22") (pinfunction "RXD0_22") (pintype "passive"))
    )
    (net (code "99") (name "unconnected-(U14-RXD1-Pad23)") (class "Default")
      (node (ref "U14") (pin "23") (pinfunction "RXD1_23") (pintype "passive"))
    )
    (net (code "100") (name "unconnected-(U14-RXIN0-Pad45)") (class "Default")
      (node (ref "U14") (pin "45") (pinfunction "RXIN0_45") (pintype "passive"))
    )
    (net (code "101") (name "unconnected-(U14-RXIN1-Pad3)") (class "Default")
      (node (ref "U14") (pin "3") (pinfunction "RXIN1_3") (pintype "passive"))
    )
    (net (code "102") (name "unconnected-(U14-RXIN2-Pad9)") (class "Default")
      (node (ref "U14") (pin "9") (pinfunction "RXIN2_9") (pintype "passive+no_connect"))
    )
    (net (code "103") (name "unconnected-(U14-RXIP0-Pad44)") (class "Default")
      (node (ref "U14") (pin "44") (pinfunction "RXIP0_44") (pintype "passive"))
    )
    (net (code "104") (name "unconnected-(U14-RXIP1-Pad4)") (class "Default")
      (node (ref "U14") (pin "4") (pinfunction "RXIP1_4") (pintype "passive"))
    )
    (net (code "105") (name "unconnected-(U14-RXIP2-Pad8)") (class "Default")
      (node (ref "U14") (pin "8") (pinfunction "RXIP2_8") (pintype "passive+no_connect"))
    )
    (net (code "106") (name "unconnected-(U14-SCL{slash}MDC-Pad27)") (class "Default")
      (node (ref "U14") (pin "27") (pinfunction "SCL/MDC_27") (pintype "passive"))
    )
    (net (code "107") (name "unconnected-(U14-SDA{slash}MDIO-Pad28)") (class "Default")
      (node (ref "U14") (pin "28") (pinfunction "SDA/MDIO_28") (pintype "passive"))
    )
    (net (code "108") (name "unconnected-(U14-SPD_STA-Pad14)") (class "Default")
      (node (ref "U14") (pin "14") (pinfunction "SPD_STA_14") (pintype "passive"))
    )
    (net (code "109") (name "unconnected-(U14-TXD0{slash}IF_SEL[0]-Pad16)") (class "Default")
      (node (ref "U14") (pin "16") (pinfunction "TXD0/IF_SEL[0]_16") (pintype "passive"))
    )
    (net (code "110") (name "unconnected-(U14-TXD1{slash}CLK_DIR-Pad15)") (class "Default")
      (node (ref "U14") (pin "15") (pinfunction "TXD1/CLK_DIR_15") (pintype "passive"))
    )
    (net (code "111") (name "unconnected-(U14-TXEN-Pad17)") (class "Default")
      (node (ref "U14") (pin "17") (pinfunction "TXEN_17") (pintype "passive"))
    )
    (net (code "112") (name "unconnected-(U14-TXON0-Pad46)") (class "Default")
      (node (ref "U14") (pin "46") (pinfunction "TXON0_46") (pintype "passive"))
    )
    (net (code "113") (name "unconnected-(U14-TXON1-Pad2)") (class "Default")
      (node (ref "U14") (pin "2") (pinfunction "TXON1_2") (pintype "passive"))
    )
    (net (code "114") (name "unconnected-(U14-TXON2-Pad10)") (class "Default")
      (node (ref "U14") (pin "10") (pinfunction "TXON2_10") (pintype "passive+no_connect"))
    )
    (net (code "115") (name "unconnected-(U14-TXOP0-Pad47)") (class "Default")
      (node (ref "U14") (pin "47") (pinfunction "TXOP0_47") (pintype "passive"))
    )
    (net (code "116") (name "unconnected-(U14-TXOP1-Pad1)") (class "Default")
      (node (ref "U14") (pin "1") (pinfunction "TXOP1_1") (pintype "passive"))
    )
    (net (code "117") (name "unconnected-(U14-TXOP2-Pad11)") (class "Default")
      (node (ref "U14") (pin "11") (pinfunction "TXOP2_11") (pintype "passive+no_connect"))
    )
    (net (code "118") (name "unconnected-(U14-V10OUT-Pad36)") (class "Default")
      (node (ref "U14") (pin "36") (pinfunction "V10OUT_36") (pintype "passive"))
    )
    (net (code "119") (name "unconnected-(U14-V33IN-Pad37)") (class "Default")
      (node (ref "U14") (pin "37") (pinfunction "V33IN_37") (pintype "passive"))
    )
    (net (code "120") (name "unconnected-(U14-XI-Pad40)") (class "Default")
      (node (ref "U14") (pin "40") (pinfunction "XI_40") (pintype "passive"))
    )
    (net (code "121") (name "unconnected-(U14-XO-Pad39)") (class "Default")
      (node (ref "U14") (pin "39") (pinfunction "XO_39") (pintype "passive"))
    )
    (net (code "122") (name "unconnected-(U15-GND-Pad2)") (class "Default")
      (node (ref "U15") (pin "2") (pinfunction "GND_2") (pintype "passive"))
    )
    (net (code "123") (name "unconnected-(U15-I{slash}O1-Pad1)") (class "Default")
      (node (ref "U15") (pin "1") (pinfunction "I/O1_1") (pintype "passive"))
    )
    (net (code "124") (name "unconnected-(U15-I{slash}O2-Pad6)") (class "Default")
      (node (ref "U15") (pin "6") (pinfunction "I/O2_6") (pintype "passive"))
    )
    (net (code "125") (name "unconnected-(U15-I{slash}O3-Pad3)") (class "Default")
      (node (ref "U15") (pin "3") (pinfunction "I/O3_3") (pintype "passive"))
    )
    (net (code "126") (name "unconnected-(U15-I{slash}O4-Pad4)") (class "Default")
      (node (ref "U15") (pin "4") (pinfunction "I/O4_4") (pintype "passive"))
    )
    (net (code "127") (name "unconnected-(U15-VCC-Pad5)") (class "Default")
      (node (ref "U15") (pin "5") (pinfunction "VCC_5") (pintype "passive"))
    )
    (net (code "128") (name "unconnected-(Y1-Pad1)") (class "Default")
      (node (ref "Y1") (pin "1") (pinfunction "1_1") (pintype "passive"))
    )
    (net (code "129") (name "unconnected-(Y1-Pad2)") (class "Default")
      (node (ref "Y1") (pin "2") (pinfunction "2_2") (pintype "passive"))
    )
    (net (code "130") (name "unconnected-(Y1-Pad3)") (class "Default")
      (node (ref "Y1") (pin "3") (pinfunction "3_3") (pintype "passive"))
    )
    (net (code "131") (name "unconnected-(Y1-Pad4)") (class "Default")
      (node (ref "Y1") (pin "4") (pinfunction "4_4") (pintype "passive"))
    )
  )
)
